# serialaudio.net
KiCad netlist of a schematic drawn in EAGLE
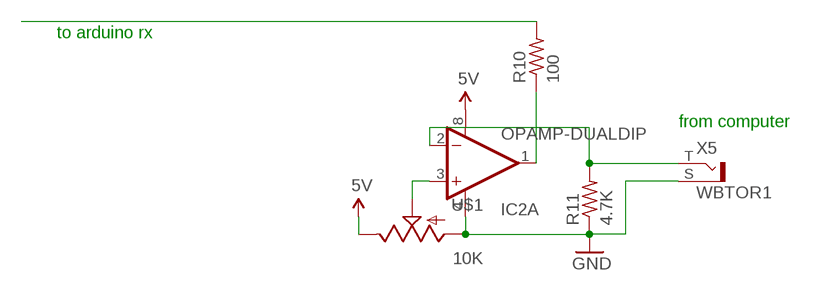
[diagram p0: schematic, sheet 1]

(export (version "E")
  (design (tool "Eeschema 10.0.6"))
  (components
    (comp (ref "IC2")
      (value "OPAMP-DUALDIP")
      (footprint "eagle-import:DIP08")
      (libsource (lib "eagle-import") (part "OPAMP-DUALDIP"))
    )
    (comp (ref "R10")
      (value "100")
      (footprint "eagle-import:0204V")
      (libsource (lib "eagle-import") (part "R-US_0204/2V"))
    )
    (comp (ref "R11")
      (value "4.7K")
      (footprint "eagle-import:0204V")
      (libsource (lib "eagle-import") (part "R-US_0204/2V"))
    )
    (comp (ref "U$1")
      (value "10K")
      (footprint "eagle-import:TRIM_POT")
      (libsource (lib "eagle-import") (part "POTTRIM"))
    )
    (comp (ref "X5")
      (value "WBTOR1")
      (footprint "eagle-import:WBTOR1")
      (fields (field (name "MPN") "WBTOR 1 BLACK"))
      (libsource (lib "eagle-import") (part "WBTOR1"))
    )
  )
  (nets
    (net (code "1") (name "5V") (class "Default")
      (node (ref "IC2") (pin "8") (pinfunction "V+_8") (pintype "power_in"))
      (node (ref "U$1") (pin "2") (pinfunction "E_2") (pintype "passive"))
    )
    (net (code "2") (name "GND") (class "Default")
      (node (ref "IC2") (pin "4") (pinfunction "V-_4") (pintype "power_in"))
      (node (ref "R11") (pin "1") (pinfunction "1_1") (pintype "passive"))
      (node (ref "U$1") (pin "3") (pinfunction "A_3") (pintype "passive"))
      (node (ref "X5") (pin "S") (pinfunction "S_S") (pintype "passive"))
    )
    (net (code "3") (name "Net-(IC2A-+IN)") (class "Default")
      (node (ref "IC2") (pin "3") (pinfunction "+IN_3") (pintype "input"))
      (node (ref "U$1") (pin "1") (pinfunction "S_1") (pintype "passive"))
    )
    (net (code "4") (name "Net-(IC2A--IN)") (class "Default")
      (node (ref "IC2") (pin "2") (pinfunction "-IN_2") (pintype "input"))
      (node (ref "R11") (pin "2") (pinfunction "2_2") (pintype "passive"))
      (node (ref "X5") (pin "T") (pinfunction "T_T") (pintype "passive"))
    )
    (net (code "5") (name "Net-(IC2A-OUT)") (class "Default")
      (node (ref "IC2") (pin "1") (pinfunction "OUT_1") (pintype "output"))
      (node (ref "R10") (pin "1") (pinfunction "1_1") (pintype "passive"))
    )
    (net (code "6") (name "unconnected-(R10-Pad2)") (class "Default")
      (node (ref "R10") (pin "2") (pinfunction "2_2") (pintype "passive"))
    )
  )
)
